# Reciever_Circuit.net
KiCad netlist of a schematic drawn in EAGLE
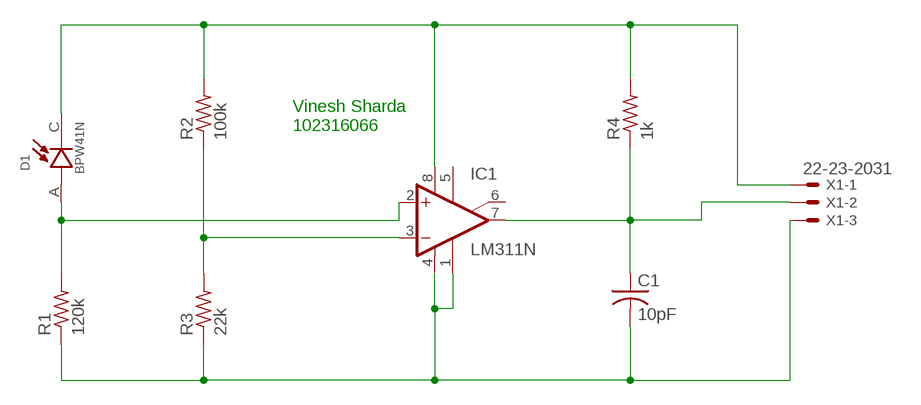
[diagram p0: schematic, sheet 1]

(export (version "E")
  (design (tool "Eeschema 10.0.6"))
  (components
    (comp (ref "C1")
      (value "10pF")
      (footprint "eagle-import:C025-024X044")
      (libsource (lib "eagle-import") (part "C-US025-024X044"))
    )
    (comp (ref "D1")
      (value "BPW41N")
      (footprint "eagle-import:DIO_BPW41N")
      (fields (field (name "MF") "Vishay Semiconductor Opto Division"))
      (libsource (lib "eagle-import") (part "BPW41N"))
    )
    (comp (ref "IC1")
      (value "LM311N")
      (footprint "eagle-import:DIL08")
      (libsource (lib "eagle-import") (part "LM311N"))
    )
    (comp (ref "R1")
      (value "120k")
      (footprint "eagle-import:0204_5")
      (libsource (lib "eagle-import") (part "R-US_0204/5"))
    )
    (comp (ref "R2")
      (value "100k")
      (footprint "eagle-import:0204_5")
      (libsource (lib "eagle-import") (part "R-US_0204/5"))
    )
    (comp (ref "R3")
      (value "22k")
      (footprint "eagle-import:0204_5")
      (libsource (lib "eagle-import") (part "R-US_0204/5"))
    )
    (comp (ref "R4")
      (value "1k")
      (footprint "eagle-import:0204_5")
      (libsource (lib "eagle-import") (part "R-US_0204/5"))
    )
    (comp (ref "X1")
      (value "22-23-2031")
      (footprint "eagle-import:22-23-2031")
      (fields (field (name "MF") "MOLEX"))
      (libsource (lib "eagle-import") (part "22-23-2031"))
    )
  )
  (nets
    (net (code "1") (name "Net-(IC1-+IN)") (class "Default")
      (node (ref "D1") (pin "A") (pinfunction "A_A") (pintype "passive"))
      (node (ref "IC1") (pin "2") (pinfunction "+IN_2") (pintype "input"))
      (node (ref "R1") (pin "2") (pinfunction "2_2") (pintype "passive"))
    )
    (net (code "2") (name "Net-(IC1--IN)") (class "Default")
      (node (ref "IC1") (pin "3") (pinfunction "-IN_3") (pintype "input"))
      (node (ref "R2") (pin "1") (pinfunction "1_1") (pintype "passive"))
      (node (ref "R3") (pin "2") (pinfunction "2_2") (pintype "passive"))
    )
    (net (code "3") (name "Net-(IC1-GND)") (class "Default")
      (node (ref "C1") (pin "2") (pinfunction "2_2") (pintype "passive"))
      (node (ref "IC1") (pin "1") (pinfunction "GND_1") (pintype "passive"))
      (node (ref "IC1") (pin "4") (pinfunction "V-_4") (pintype "power_in"))
      (node (ref "R1") (pin "1") (pinfunction "1_1") (pintype "passive"))
      (node (ref "R3") (pin "1") (pinfunction "1_1") (pintype "passive"))
      (node (ref "X1") (pin "3") (pinfunction "S_3") (pintype "passive"))
    )
    (net (code "4") (name "Net-(IC1-OUT)") (class "Default")
      (node (ref "C1") (pin "1") (pinfunction "1_1") (pintype "passive"))
      (node (ref "IC1") (pin "7") (pinfunction "OUT_7") (pintype "output"))
      (node (ref "R4") (pin "1") (pinfunction "1_1") (pintype "passive"))
      (node (ref "X1") (pin "2") (pinfunction "S_2") (pintype "passive"))
    )
    (net (code "5") (name "Net-(IC1-V+)") (class "Default")
      (node (ref "D1") (pin "C") (pinfunction "C_C") (pintype "passive"))
      (node (ref "IC1") (pin "8") (pinfunction "V+_8") (pintype "power_in"))
      (node (ref "R2") (pin "2") (pinfunction "2_2") (pintype "passive"))
      (node (ref "R4") (pin "2") (pinfunction "2_2") (pintype "passive"))
      (node (ref "X1") (pin "1") (pinfunction "S_1") (pintype "passive"))
    )
    (net (code "6") (name "unconnected-(IC1-ON-Pad5)") (class "Default")
      (node (ref "IC1") (pin "5") (pinfunction "ON_5") (pintype "passive"))
    )
    (net (code "7") (name "unconnected-(IC1-ON{slash}STR-Pad6)") (class "Default")
      (node (ref "IC1") (pin "6") (pinfunction "ON/STR_6") (pintype "passive"))
    )
  )
)
